# XCOMBO_A.net
KiCad netlist of a schematic drawn in EAGLE
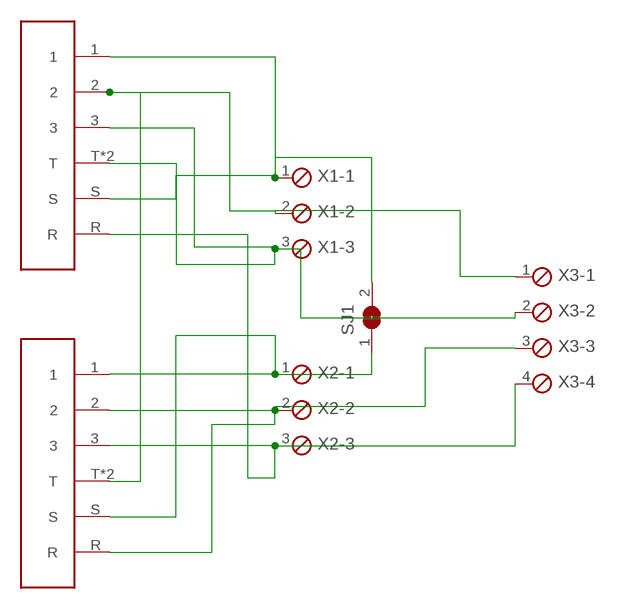
[diagram p0: schematic, sheet 1]

(export (version "E")
  (design (tool "Eeschema 10.0.6"))
  (components
    (comp (ref "SJ1") (value "SJ") (footprint "eagle-import:SJ") (libsource (lib "eagle-import") (part "SJ")))
    (comp (ref "U$1")
      (value "XLRCOMBOTYPEA")
      (footprint "eagle-import:NCJ6FA-V-0")
      (libsource (lib "eagle-import") (part "XLRCOMBOTYPEA"))
    )
    (comp (ref "U$2")
      (value "XLRCOMBOTYPEA")
      (footprint "eagle-import:NCJ6FA-V-0")
      (libsource (lib "eagle-import") (part "XLRCOMBOTYPEA"))
    )
    (comp (ref "X1")
      (value "MPT3")
      (footprint "eagle-import:3POL254")
      (libsource (lib "eagle-import") (part "MPT3"))
    )
    (comp (ref "X2")
      (value "MPT3")
      (footprint "eagle-import:3POL254")
      (libsource (lib "eagle-import") (part "MPT3"))
    )
    (comp (ref "X3")
      (value "MPT4")
      (footprint "eagle-import:4POL254")
      (libsource (lib "eagle-import") (part "MPT4"))
    )
  )
  (nets
    (net (code "1") (name "Net-(SJ1-Pad1)") (class "Default")
      (node (ref "SJ1") (pin "1") (pinfunction "1_1") (pintype "passive"))
      (node (ref "U$1") (pin "1") (pinfunction "1_1") (pintype "bidirectional"))
      (node (ref "U$1") (pin "S") (pinfunction "S_S") (pintype "bidirectional"))
      (node (ref "X2") (pin "1") (pinfunction "1_1") (pintype "passive"))
    )
    (net (code "2") (name "Net-(SJ1-Pad2)") (class "Default")
      (node (ref "SJ1") (pin "2") (pinfunction "2_2") (pintype "passive"))
      (node (ref "U$2") (pin "1") (pinfunction "1_1") (pintype "bidirectional"))
      (node (ref "U$2") (pin "S") (pinfunction "S_S") (pintype "bidirectional"))
      (node (ref "X1") (pin "1") (pinfunction "1_1") (pintype "passive"))
    )
    (net (code "3") (name "Net-(X1B-1)") (class "Default")
      (node (ref "U$1") (pin "T") (pinfunction "T_T") (pintype "bidirectional"))
      (node (ref "U$1") (pin "T2") (pinfunction "T_T2") (pintype "bidirectional"))
      (node (ref "U$2") (pin "2") (pinfunction "2_2") (pintype "bidirectional"))
      (node (ref "X1") (pin "2") (pinfunction "1_2") (pintype "passive"))
      (node (ref "X3") (pin "1") (pinfunction "1_1") (pintype "passive"))
    )
    (net (code "4") (name "Net-(X1C-1)") (class "Default")
      (node (ref "U$2") (pin "3") (pinfunction "3_3") (pintype "bidirectional"))
      (node (ref "U$2") (pin "T") (pinfunction "T_T") (pintype "bidirectional"))
      (node (ref "U$2") (pin "T2") (pinfunction "T_T2") (pintype "bidirectional"))
      (node (ref "X1") (pin "3") (pinfunction "1_3") (pintype "passive"))
      (node (ref "X3") (pin "2") (pinfunction "1_2") (pintype "passive"))
    )
    (net (code "5") (name "Net-(X2B-1)") (class "Default")
      (node (ref "U$1") (pin "2") (pinfunction "2_2") (pintype "bidirectional"))
      (node (ref "U$1") (pin "R") (pinfunction "R_R") (pintype "bidirectional"))
      (node (ref "X2") (pin "2") (pinfunction "1_2") (pintype "passive"))
      (node (ref "X3") (pin "3") (pinfunction "1_3") (pintype "passive"))
    )
    (net (code "6") (name "Net-(X2C-1)") (class "Default")
      (node (ref "U$1") (pin "3") (pinfunction "3_3") (pintype "bidirectional"))
      (node (ref "U$2") (pin "R") (pinfunction "R_R") (pintype "bidirectional"))
      (node (ref "X2") (pin "3") (pinfunction "1_3") (pintype "passive"))
      (node (ref "X3") (pin "4") (pinfunction "1_4") (pintype "passive"))
    )
  )
)
